# ProDocument_Affordable_2023-07-23.net
KiCad netlist of a schematic drawn in EasyEDA Pro
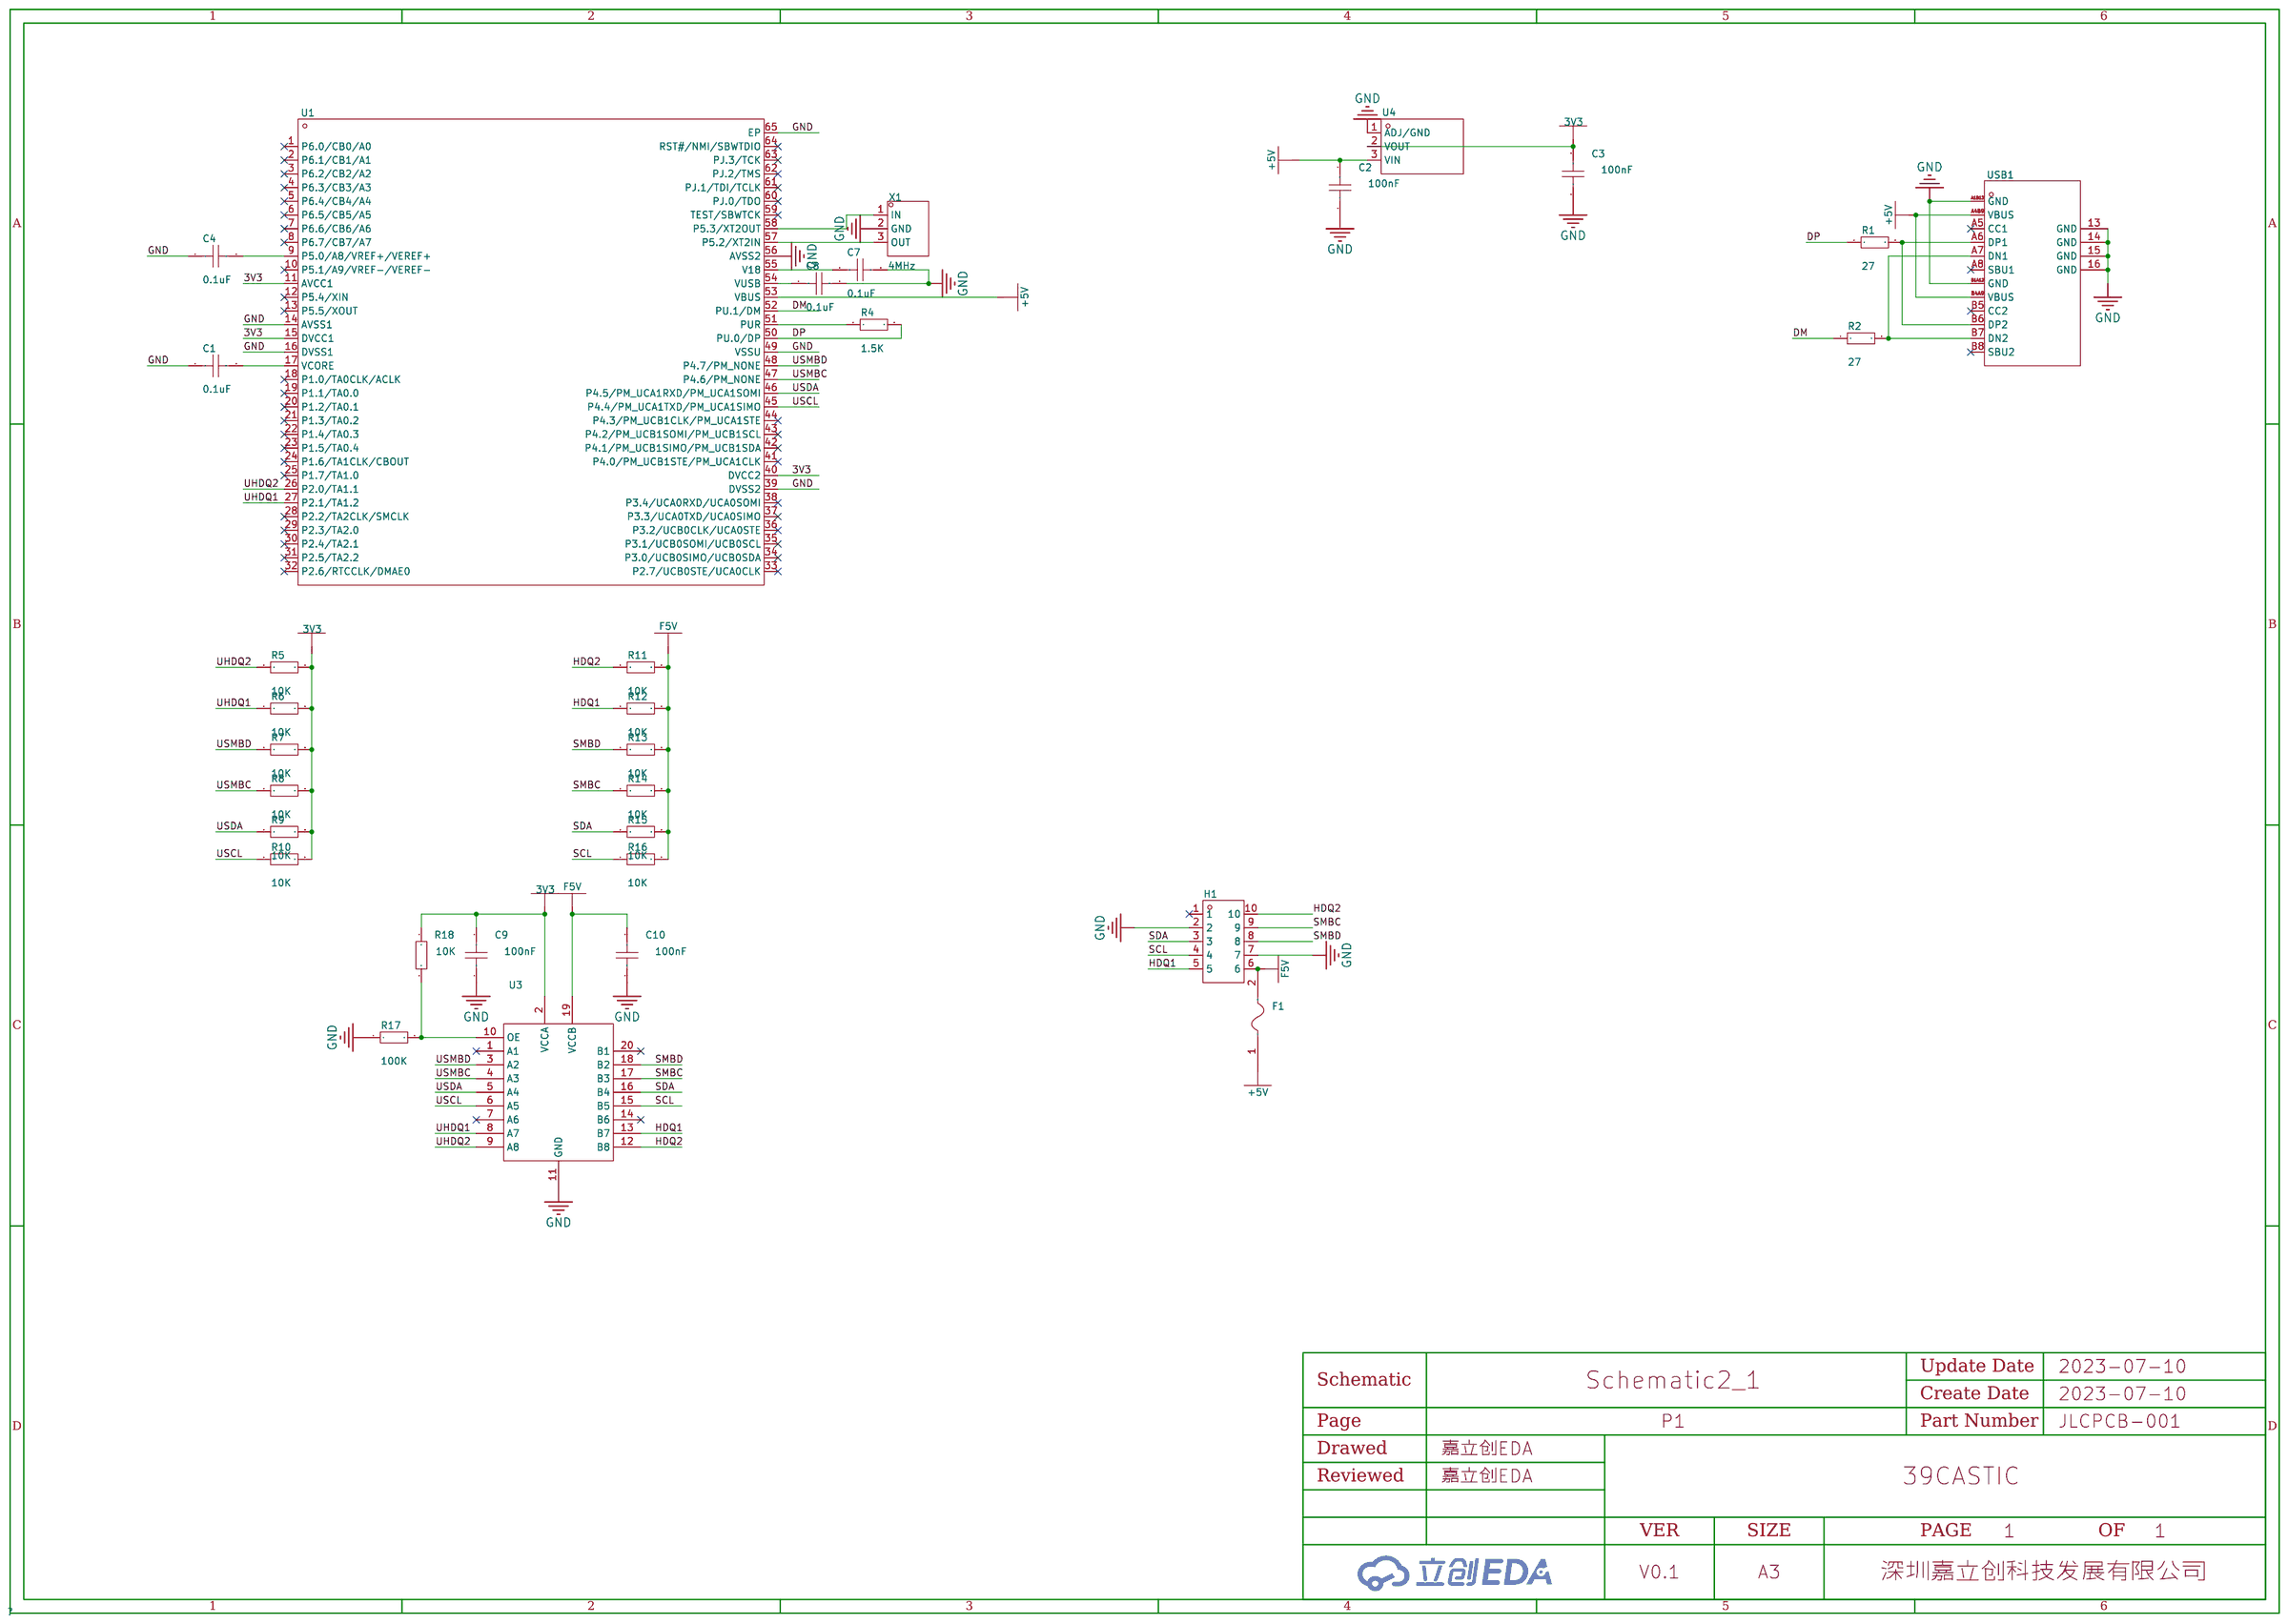
[diagram p0: schematic sheet]

(export (version "E")
  (design (tool "Eeschema 10.0.6"))
  (components
    (comp (ref "C1")
      (value "0.1uF")
      (footprint "easyedapro:C0603_1")
      (description "容值:100nF;精度:±10%;额定电压:50V;温度系数:X7R;")
      (libsource (lib "easyedapro") (part "C1210X7R475K630NT"))
    )
    (comp (ref "C2")
      (value "100nF")
      (footprint "easyedapro:C0603_1")
      (description "容值:100nF;精度:±10%;额定电压:50V;温度系数:X7R;")
      (libsource (lib "easyedapro") (part "C1210X7R475K630NT"))
    )
    (comp (ref "C3")
      (value "100nF")
      (footprint "easyedapro:C0603_1")
      (description "容值:100nF;精度:±10%;额定电压:50V;温度系数:X7R;")
      (libsource (lib "easyedapro") (part "C1210X7R475K630NT"))
    )
    (comp (ref "C4")
      (value "0.1uF")
      (footprint "easyedapro:C0603_1")
      (description "容值:100nF;精度:±10%;额定电压:50V;温度系数:X7R;")
      (libsource (lib "easyedapro") (part "C1210X7R475K630NT"))
    )
    (comp (ref "C7")
      (value "0.1uF")
      (footprint "easyedapro:C0603_1")
      (description "容值:100nF;精度:±10%;额定电压:50V;温度系数:X7R;")
      (libsource (lib "easyedapro") (part "C1210X7R475K630NT"))
    )
    (comp (ref "C8")
      (value "0.1uF")
      (footprint "easyedapro:C0603_1")
      (description "容值:100nF;精度:±10%;额定电压:50V;温度系数:X7R;")
      (libsource (lib "easyedapro") (part "C1210X7R475K630NT"))
    )
    (comp (ref "C9")
      (value "100nF")
      (footprint "easyedapro:C0603_1")
      (description "容值:100nF;精度:±10%;额定电压:50V;温度系数:X7R;")
      (libsource (lib "easyedapro") (part "C1210X7R475K630NT"))
    )
    (comp (ref "C10")
      (value "100nF")
      (footprint "easyedapro:C0603_1")
      (description "容值:100nF;精度:±10%;额定电压:50V;温度系数:X7R;")
      (libsource (lib "easyedapro") (part "C1210X7R475K630NT"))
    )
    (comp (ref "F1")
      (value "~")
      (footprint "easyedapro:F0805")
      (description "最大电压:6V;最大电流:40A;保持电流:500mA;跳闸电流:1A;")
      (fields (field (name "Manufacturer Part") "MF-PSMF050X-2") (field (name "Manufacturer") "BOURNS"))
      (libsource (lib "easyedapro") (part "MF-PSMF050X-2"))
    )
    (comp (ref "H1")
      (value "2*5p夹板_2.54mm")
      (footprint "easyedapro:2*5P_夹板_2.54MM")
      (libsource (lib "easyedapro") (part "2X5P 2.54 排母"))
    )
    (comp (ref "R1")
      (value "27")
      (footprint "easyedapro:R0603_1")
      (libsource (lib "easyedapro") (part "电阻_1"))
    )
    (comp (ref "R2")
      (value "27")
      (footprint "easyedapro:R0603_1")
      (libsource (lib "easyedapro") (part "电阻_1"))
    )
    (comp (ref "R4")
      (value "1.5K")
      (footprint "easyedapro:R0603_1")
      (libsource (lib "easyedapro") (part "电阻_1"))
    )
    (comp (ref "R5")
      (value "10K")
      (footprint "easyedapro:R0603_1")
      (libsource (lib "easyedapro") (part "电阻_1"))
    )
    (comp (ref "R6")
      (value "10K")
      (footprint "easyedapro:R0603_1")
      (libsource (lib "easyedapro") (part "电阻_1"))
    )
    (comp (ref "R7")
      (value "10K")
      (footprint "easyedapro:R0603_1")
      (libsource (lib "easyedapro") (part "电阻_1"))
    )
    (comp (ref "R8")
      (value "10K")
      (footprint "easyedapro:R0603_1")
      (libsource (lib "easyedapro") (part "电阻_1"))
    )
    (comp (ref "R9")
      (value "10K")
      (footprint "easyedapro:R0603_1")
      (libsource (lib "easyedapro") (part "电阻_1"))
    )
    (comp (ref "R10")
      (value "10K")
      (footprint "easyedapro:R0603_1")
      (libsource (lib "easyedapro") (part "电阻_1"))
    )
    (comp (ref "R11")
      (value "10K")
      (footprint "easyedapro:R0603_1")
      (libsource (lib "easyedapro") (part "电阻_1"))
    )
    (comp (ref "R12")
      (value "10K")
      (footprint "easyedapro:R0603_1")
      (libsource (lib "easyedapro") (part "电阻_1"))
    )
    (comp (ref "R13")
      (value "10K")
      (footprint "easyedapro:R0603_1")
      (libsource (lib "easyedapro") (part "电阻_1"))
    )
    (comp (ref "R14")
      (value "10K")
      (footprint "easyedapro:R0603_1")
      (libsource (lib "easyedapro") (part "电阻_1"))
    )
    (comp (ref "R15")
      (value "10K")
      (footprint "easyedapro:R0603_1")
      (libsource (lib "easyedapro") (part "电阻_1"))
    )
    (comp (ref "R16")
      (value "10K")
      (footprint "easyedapro:R0603_1")
      (libsource (lib "easyedapro") (part "电阻_1"))
    )
    (comp (ref "R17")
      (value "100K")
      (footprint "easyedapro:R0603_1")
      (libsource (lib "easyedapro") (part "电阻_1"))
    )
    (comp (ref "R18")
      (value "10K")
      (footprint "easyedapro:R0603_1")
      (libsource (lib "easyedapro") (part "电阻_1"))
    )
    (comp (ref "U1")
      (value "~")
      (footprint "easyedapro:QFN-64_L9.0-W9.0-P0.50-BL-EP4.3")
      (description "CPU位数:16-Bit;CPU内核:CPUXV2;主频（MAX):25MHz;工作电压:1.8V ~ 3.6V;")
      (fields (field (name "Manufacturer Part") "MSP430F5528IRGCR") (field (name "Manufacturer") "TI(德州仪器)"))
      (libsource (lib "easyedapro") (part "MSP430F5528IRGCR"))
    )
    (comp (ref "U3")
      (value "~")
      (footprint "easyedapro:TSSOP-20_L6.5-W4.4-P0.65-LS6.4-BL")
      (fields (field (name "Manufacturer Part") "TXS0108EPWR") (field (name "Manufacturer") "TI(德州仪器)"))
      (libsource (lib "easyedapro") (part "TXS0108EPWR"))
    )
    (comp (ref "U4")
      (value "~")
      (footprint "easyedapro:SOT-89-3_L4.5-W2.5-P1.50-LS4.2-BR")
      (description "输出类型:-;")
      (fields (field (name "Manufacturer Part") "AMS1117-5.0") (field (name "Manufacturer") "Slkor(萨科微)"))
      (libsource (lib "easyedapro") (part "AMS1117-5.0_C880753"))
    )
    (comp (ref "USB1")
      (value "~")
      (footprint "easyedapro:USB-C-SMD_TYPEC-304-BCP16")
      (description "连接器类型:Type-C;标准:USB 3.1;公母:母座;触点数量:16.0;端口数量:1;安装方式:卧贴;额定电流 - 电源:3A;工作温度范围:-25~+85;焊接温度(最大值):260;")
      (fields (field (name "Manufacturer Part") "TYPEC-304-BCP16") (field (name "Manufacturer") "XUNPU(讯普)"))
      (libsource (lib "easyedapro") (part "TYPEC-304-BCP16"))
    )
    (comp (ref "X1")
      (value "4MHz")
      (footprint "easyedapro:OSC-SMD_3P-L4.5-W2.0")
      (description "频率:4MHz;频率容差:±0.5%;内藏负载电容:39pF;谐振阻抗:60Ω;")
      (fields
        (field (name "Manufacturer Part") "CSTCR4M00G55B-R0")
        (field (name "Manufacturer") "muRata(村田)")
      )
      (libsource (lib "easyedapro") (part "CSTCR4M00G55B-R0"))
    )
  )
  (nets
    (net (code "1") (name "+5V") (class "Default")
      (node (ref "C2") (pin "2") (pinfunction "2_2") (pintype "input"))
      (node (ref "F1") (pin "1") (pinfunction "1_1") (pintype "input"))
      (node (ref "U1") (pin "53") (pinfunction "VBUS_53") (pintype "input"))
      (node (ref "U4") (pin "3") (pinfunction "VIN_3") (pintype "input"))
      (node (ref "USB1") (pin "A4B9") (pinfunction "VBUS_A4B9") (pintype "input"))
      (node (ref "USB1") (pin "B4A9") (pinfunction "VBUS_B4A9") (pintype "input"))
    )
    (net (code "2") (name "/DM") (class "Default")
      (node (ref "R2") (pin "1") (pinfunction "1_1") (pintype "input"))
      (node (ref "U1") (pin "52") (pinfunction "PU.1/DM_52") (pintype "input"))
    )
    (net (code "3") (name "/DP") (class "Default")
      (node (ref "R1") (pin "1") (pinfunction "1_1") (pintype "input"))
      (node (ref "R4") (pin "2") (pinfunction "2_2") (pintype "input"))
      (node (ref "U1") (pin "50") (pinfunction "PU.0/DP_50") (pintype "input"))
    )
    (net (code "4") (name "/HDQ1") (class "Default")
      (node (ref "H1") (pin "5") (pinfunction "5_5") (pintype "input"))
      (node (ref "R12") (pin "1") (pinfunction "1_1") (pintype "input"))
      (node (ref "U3") (pin "13") (pinfunction "B7_13") (pintype "input"))
    )
    (net (code "5") (name "/HDQ2") (class "Default")
      (node (ref "H1") (pin "10") (pinfunction "10_10") (pintype "input"))
      (node (ref "R11") (pin "1") (pinfunction "1_1") (pintype "input"))
      (node (ref "U3") (pin "12") (pinfunction "B8_12") (pintype "input"))
    )
    (net (code "6") (name "/SCL") (class "Default")
      (node (ref "H1") (pin "4") (pinfunction "4_4") (pintype "input"))
      (node (ref "R16") (pin "1") (pinfunction "1_1") (pintype "input"))
      (node (ref "U3") (pin "15") (pinfunction "B5_15") (pintype "input"))
    )
    (net (code "7") (name "/SDA") (class "Default")
      (node (ref "H1") (pin "3") (pinfunction "3_3") (pintype "input"))
      (node (ref "R15") (pin "1") (pinfunction "1_1") (pintype "input"))
      (node (ref "U3") (pin "16") (pinfunction "B4_16") (pintype "input"))
    )
    (net (code "8") (name "/SMBC") (class "Default")
      (node (ref "H1") (pin "9") (pinfunction "9_9") (pintype "input"))
      (node (ref "R14") (pin "1") (pinfunction "1_1") (pintype "input"))
      (node (ref "U3") (pin "17") (pinfunction "B3_17") (pintype "input"))
    )
    (net (code "9") (name "/SMBD") (class "Default")
      (node (ref "H1") (pin "8") (pinfunction "8_8") (pintype "input"))
      (node (ref "R13") (pin "1") (pinfunction "1_1") (pintype "input"))
      (node (ref "U3") (pin "18") (pinfunction "B2_18") (pintype "input"))
    )
    (net (code "10") (name "/UHDQ1") (class "Default")
      (node (ref "R6") (pin "1") (pinfunction "1_1") (pintype "input"))
      (node (ref "U1") (pin "27") (pinfunction "P2.1/TA1.2_27") (pintype "input"))
      (node (ref "U3") (pin "8") (pinfunction "A7_8") (pintype "input"))
    )
    (net (code "11") (name "/UHDQ2") (class "Default")
      (node (ref "R5") (pin "1") (pinfunction "1_1") (pintype "input"))
      (node (ref "U1") (pin "26") (pinfunction "P2.0/TA1.1_26") (pintype "input"))
      (node (ref "U3") (pin "9") (pinfunction "A8_9") (pintype "input"))
    )
    (net (code "12") (name "/USCL") (class "Default")
      (node (ref "R10") (pin "1") (pinfunction "1_1") (pintype "input"))
      (node (ref "U1") (pin "45") (pinfunction "P4.4/PM_UCA1TXD/PM_UCA1SIMO_45") (pintype "input"))
      (node (ref "U3") (pin "6") (pinfunction "A5_6") (pintype "input"))
    )
    (net (code "13") (name "/USDA") (class "Default")
      (node (ref "R9") (pin "1") (pinfunction "1_1") (pintype "input"))
      (node (ref "U1") (pin "46") (pinfunction "P4.5/PM_UCA1RXD/PM_UCA1SOMI_46") (pintype "input"))
      (node (ref "U3") (pin "5") (pinfunction "A4_5") (pintype "input"))
    )
    (net (code "14") (name "/USMBC") (class "Default")
      (node (ref "R8") (pin "1") (pinfunction "1_1") (pintype "input"))
      (node (ref "U1") (pin "47") (pinfunction "P4.6/PM_NONE_47") (pintype "input"))
      (node (ref "U3") (pin "4") (pinfunction "A3_4") (pintype "input"))
    )
    (net (code "15") (name "/USMBD") (class "Default")
      (node (ref "R7") (pin "1") (pinfunction "1_1") (pintype "input"))
      (node (ref "U1") (pin "48") (pinfunction "P4.7/PM_NONE_48") (pintype "input"))
      (node (ref "U3") (pin "3") (pinfunction "A2_3") (pintype "input"))
    )
    (net (code "16") (name "3V3") (class "Default")
      (node (ref "C3") (pin "2") (pinfunction "2_2") (pintype "input"))
      (node (ref "C9") (pin "2") (pinfunction "2_2") (pintype "input"))
      (node (ref "R10") (pin "2") (pinfunction "2_2") (pintype "input"))
      (node (ref "R18") (pin "2") (pinfunction "2_2") (pintype "input"))
      (node (ref "R5") (pin "2") (pinfunction "2_2") (pintype "input"))
      (node (ref "R6") (pin "2") (pinfunction "2_2") (pintype "input"))
      (node (ref "R7") (pin "2") (pinfunction "2_2") (pintype "input"))
      (node (ref "R8") (pin "2") (pinfunction "2_2") (pintype "input"))
      (node (ref "R9") (pin "2") (pinfunction "2_2") (pintype "input"))
      (node (ref "U1") (pin "11") (pinfunction "AVCC1_11") (pintype "input"))
      (node (ref "U1") (pin "15") (pinfunction "DVCC1_15") (pintype "input"))
      (node (ref "U1") (pin "40") (pinfunction "DVCC2_40") (pintype "input"))
      (node (ref "U3") (pin "2") (pinfunction "VCCA_2") (pintype "input"))
      (node (ref "U4") (pin "2") (pinfunction "VOUT_2") (pintype "input"))
    )
    (net (code "17") (name "F5V") (class "Default")
      (node (ref "C10") (pin "2") (pinfunction "2_2") (pintype "input"))
      (node (ref "F1") (pin "2") (pinfunction "2_2") (pintype "input"))
      (node (ref "H1") (pin "6") (pinfunction "6_6") (pintype "input"))
      (node (ref "R11") (pin "2") (pinfunction "2_2") (pintype "input"))
      (node (ref "R12") (pin "2") (pinfunction "2_2") (pintype "input"))
      (node (ref "R13") (pin "2") (pinfunction "2_2") (pintype "input"))
      (node (ref "R14") (pin "2") (pinfunction "2_2") (pintype "input"))
      (node (ref "R15") (pin "2") (pinfunction "2_2") (pintype "input"))
      (node (ref "R16") (pin "2") (pinfunction "2_2") (pintype "input"))
      (node (ref "U3") (pin "19") (pinfunction "VCCB_19") (pintype "input"))
    )
    (net (code "18") (name "GND") (class "Default")
      (node (ref "C1") (pin "1") (pinfunction "1_1") (pintype "input"))
      (node (ref "C10") (pin "1") (pinfunction "1_1") (pintype "input"))
      (node (ref "C2") (pin "1") (pinfunction "1_1") (pintype "input"))
      (node (ref "C3") (pin "1") (pinfunction "1_1") (pintype "input"))
      (node (ref "C4") (pin "1") (pinfunction "1_1") (pintype "input"))
      (node (ref "C7") (pin "2") (pinfunction "2_2") (pintype "input"))
      (node (ref "C8") (pin "2") (pinfunction "2_2") (pintype "input"))
      (node (ref "C9") (pin "1") (pinfunction "1_1") (pintype "input"))
      (node (ref "H1") (pin "2") (pinfunction "2_2") (pintype "input"))
      (node (ref "H1") (pin "7") (pinfunction "7_7") (pintype "input"))
      (node (ref "R17") (pin "1") (pinfunction "1_1") (pintype "input"))
      (node (ref "U1") (pin "14") (pinfunction "AVSS1_14") (pintype "input"))
      (node (ref "U1") (pin "16") (pinfunction "DVSS1_16") (pintype "input"))
      (node (ref "U1") (pin "39") (pinfunction "DVSS2_39") (pintype "input"))
      (node (ref "U1") (pin "49") (pinfunction "VSSU_49") (pintype "input"))
      (node (ref "U1") (pin "56") (pinfunction "AVSS2_56") (pintype "input"))
      (node (ref "U1") (pin "65") (pinfunction "EP_65") (pintype "input"))
      (node (ref "U3") (pin "11") (pinfunction "GND_11") (pintype "input"))
      (node (ref "U4") (pin "1") (pinfunction "ADJ/GND_1") (pintype "input"))
      (node (ref "USB1") (pin "13") (pinfunction "GND_13") (pintype "input"))
      (node (ref "USB1") (pin "14") (pinfunction "GND_14") (pintype "input"))
      (node (ref "USB1") (pin "15") (pinfunction "GND_15") (pintype "input"))
      (node (ref "USB1") (pin "16") (pinfunction "GND_16") (pintype "input"))
      (node (ref "USB1") (pin "A1B12") (pinfunction "GND_A1B12") (pintype "input"))
      (node (ref "USB1") (pin "B1A12") (pinfunction "GND_B1A12") (pintype "input"))
      (node (ref "X1") (pin "2") (pinfunction "GND_2") (pintype "input"))
    )
    (net (code "19") (name "Net-(U1-P5.0{slash}A8{slash}VREF+{slash}VEREF+)") (class "Default")
      (node (ref "C4") (pin "2") (pinfunction "2_2") (pintype "input"))
      (node (ref "U1") (pin "9") (pinfunction "P5.0/A8/VREF+/VEREF+_9") (pintype "input"))
    )
    (net (code "20") (name "Net-(U1-P5.2{slash}XT2IN)") (class "Default")
      (node (ref "U1") (pin "57") (pinfunction "P5.2/XT2IN_57") (pintype "input"))
      (node (ref "X1") (pin "3") (pinfunction "OUT_3") (pintype "input"))
    )
    (net (code "21") (name "Net-(U1-P5.3{slash}XT2OUT)") (class "Default")
      (node (ref "U1") (pin "58") (pinfunction "P5.3/XT2OUT_58") (pintype "input"))
      (node (ref "X1") (pin "1") (pinfunction "IN_1") (pintype "input"))
    )
    (net (code "22") (name "Net-(U1-PUR)") (class "Default")
      (node (ref "R4") (pin "1") (pinfunction "1_1") (pintype "input"))
      (node (ref "U1") (pin "51") (pinfunction "PUR_51") (pintype "input"))
    )
    (net (code "23") (name "Net-(U1-V18)") (class "Default")
      (node (ref "C7") (pin "1") (pinfunction "1_1") (pintype "input"))
      (node (ref "U1") (pin "55") (pinfunction "V18_55") (pintype "input"))
    )
    (net (code "24") (name "Net-(U1-VCORE)") (class "Default")
      (node (ref "C1") (pin "2") (pinfunction "2_2") (pintype "input"))
      (node (ref "U1") (pin "17") (pinfunction "VCORE_17") (pintype "input"))
    )
    (net (code "25") (name "Net-(U1-VUSB)") (class "Default")
      (node (ref "C8") (pin "1") (pinfunction "1_1") (pintype "input"))
      (node (ref "U1") (pin "54") (pinfunction "VUSB_54") (pintype "input"))
    )
    (net (code "26") (name "Net-(U3-OE)") (class "Default")
      (node (ref "R17") (pin "2") (pinfunction "2_2") (pintype "input"))
      (node (ref "R18") (pin "1") (pinfunction "1_1") (pintype "input"))
      (node (ref "U3") (pin "10") (pinfunction "OE_10") (pintype "input"))
    )
    (net (code "27") (name "Net-(USB1-DN1)") (class "Default")
      (node (ref "R2") (pin "2") (pinfunction "2_2") (pintype "input"))
      (node (ref "USB1") (pin "A7") (pinfunction "DN1_A7") (pintype "input"))
      (node (ref "USB1") (pin "B7") (pinfunction "DN2_B7") (pintype "input"))
    )
    (net (code "28") (name "Net-(USB1-DP1)") (class "Default")
      (node (ref "R1") (pin "2") (pinfunction "2_2") (pintype "input"))
      (node (ref "USB1") (pin "A6") (pinfunction "DP1_A6") (pintype "input"))
      (node (ref "USB1") (pin "B6") (pinfunction "DP2_B6") (pintype "input"))
    )
    (net (code "29") (name "unconnected-(H1-Pad1)") (class "Default")
      (node (ref "H1") (pin "1") (pinfunction "1_1") (pintype "input+no_connect"))
    )
    (net (code "30") (name "unconnected-(U1-P1.0{slash}TA0CLK{slash}ACLK-Pad18)") (class "Default")
      (node (ref "U1") (pin "18") (pinfunction "P1.0/TA0CLK/ACLK_18") (pintype "input+no_connect"))
    )
    (net (code "31") (name "unconnected-(U1-P1.1{slash}TA0.0-Pad19)") (class "Default")
      (node (ref "U1") (pin "19") (pinfunction "P1.1/TA0.0_19") (pintype "input+no_connect"))
    )
    (net (code "32") (name "unconnected-(U1-P1.2{slash}TA0.1-Pad20)") (class "Default")
      (node (ref "U1") (pin "20") (pinfunction "P1.2/TA0.1_20") (pintype "input+no_connect"))
    )
    (net (code "33") (name "unconnected-(U1-P1.3{slash}TA0.2-Pad21)") (class "Default")
      (node (ref "U1") (pin "21") (pinfunction "P1.3/TA0.2_21") (pintype "input+no_connect"))
    )
    (net (code "34") (name "unconnected-(U1-P1.4{slash}TA0.3-Pad22)") (class "Default")
      (node (ref "U1") (pin "22") (pinfunction "P1.4/TA0.3_22") (pintype "input+no_connect"))
    )
    (net (code "35") (name "unconnected-(U1-P1.5{slash}TA0.4-Pad23)") (class "Default")
      (node (ref "U1") (pin "23") (pinfunction "P1.5/TA0.4_23") (pintype "input+no_connect"))
    )
    (net (code "36") (name "unconnected-(U1-P1.6{slash}TA1CLK{slash}CBOUT-Pad24)") (class "Default")
      (node (ref "U1") (pin "24") (pinfunction "P1.6/TA1CLK/CBOUT_24") (pintype "input+no_connect"))
    )
    (net (code "37") (name "unconnected-(U1-P1.7{slash}TA1.0-Pad25)") (class "Default")
      (node (ref "U1") (pin "25") (pinfunction "P1.7/TA1.0_25") (pintype "input+no_connect"))
    )
    (net (code "38") (name "unconnected-(U1-P2.2{slash}TA2CLK{slash}SMCLK-Pad28)") (class "Default")
      (node (ref "U1") (pin "28") (pinfunction "P2.2/TA2CLK/SMCLK_28") (pintype "input+no_connect"))
    )
    (net (code "39") (name "unconnected-(U1-P2.3{slash}TA2.0-Pad29)") (class "Default")
      (node (ref "U1") (pin "29") (pinfunction "P2.3/TA2.0_29") (pintype "input+no_connect"))
    )
    (net (code "40") (name "unconnected-(U1-P2.4{slash}TA2.1-Pad30)") (class "Default")
      (node (ref "U1") (pin "30") (pinfunction "P2.4/TA2.1_30") (pintype "input+no_connect"))
    )
    (net (code "41") (name "unconnected-(U1-P2.5{slash}TA2.2-Pad31)") (class "Default")
      (node (ref "U1") (pin "31") (pinfunction "P2.5/TA2.2_31") (pintype "input+no_connect"))
    )
    (net (code "42") (name "unconnected-(U1-P2.6{slash}RTCCLK{slash}DMAE0-Pad32)") (class "Default")
      (node (ref "U1") (pin "32") (pinfunction "P2.6/RTCCLK/DMAE0_32") (pintype "input+no_connect"))
    )
    (net (code "43") (name "unconnected-(U1-P2.7{slash}UCB0STE{slash}UCA0CLK-Pad33)") (class "Default")
      (node (ref "U1") (pin "33") (pinfunction "P2.7/UCB0STE/UCA0CLK_33") (pintype "input+no_connect"))
    )
    (net (code "44") (name "unconnected-(U1-P3.0{slash}UCB0SIMO{slash}UCB0SDA-Pad34)") (class "Default")
      (node (ref "U1") (pin "34") (pinfunction "P3.0/UCB0SIMO/UCB0SDA_34") (pintype "input+no_connect"))
    )
    (net (code "45") (name "unconnected-(U1-P3.1{slash}UCB0SOMI{slash}UCB0SCL-Pad35)") (class "Default")
      (node (ref "U1") (pin "35") (pinfunction "P3.1/UCB0SOMI/UCB0SCL_35") (pintype "input+no_connect"))
    )
    (net (code "46") (name "unconnected-(U1-P3.2{slash}UCB0CLK{slash}UCA0STE-Pad36)") (class "Default")
      (node (ref "U1") (pin "36") (pinfunction "P3.2/UCB0CLK/UCA0STE_36") (pintype "input+no_connect"))
    )
    (net (code "47") (name "unconnected-(U1-P3.3{slash}UCA0TXD{slash}UCA0SIMO-Pad37)") (class "Default")
      (node (ref "U1") (pin "37") (pinfunction "P3.3/UCA0TXD/UCA0SIMO_37") (pintype "input+no_connect"))
    )
    (net (code "48") (name "unconnected-(U1-P3.4{slash}UCA0RXD{slash}UCA0SOMI-Pad38)") (class "Default")
      (node (ref "U1") (pin "38") (pinfunction "P3.4/UCA0RXD/UCA0SOMI_38") (pintype "input+no_connect"))
    )
    (net (code "49") (name "unconnected-(U1-P4.0{slash}PM_UCB1STE{slash}PM_UCA1CLK-Pad41)") (class "Default")
      (node (ref "U1") (pin "41") (pinfunction "P4.0/PM_UCB1STE/PM_UCA1CLK_41") (pintype "input+no_connect"))
    )
    (net (code "50") (name "unconnected-(U1-P4.1{slash}PM_UCB1SIMO{slash}PM_UCB1SDA-Pad42)") (class "Default")
      (node (ref "U1") (pin "42") (pinfunction "P4.1/PM_UCB1SIMO/PM_UCB1SDA_42") (pintype "input+no_connect"))
    )
    (net (code "51") (name "unconnected-(U1-P4.2{slash}PM_UCB1SOMI{slash}PM_UCB1SCL-Pad43)") (class "Default")
      (node (ref "U1") (pin "43") (pinfunction "P4.2/PM_UCB1SOMI/PM_UCB1SCL_43") (pintype "input+no_connect"))
    )
    (net (code "52") (name "unconnected-(U1-P4.3{slash}PM_UCB1CLK{slash}PM_UCA1STE-Pad44)") (class "Default")
      (node (ref "U1") (pin "44") (pinfunction "P4.3/PM_UCB1CLK/PM_UCA1STE_44") (pintype "input+no_connect"))
    )
    (net (code "53") (name "unconnected-(U1-P5.1{slash}A9{slash}VREF-{slash}VEREF--Pad10)") (class "Default")
      (node (ref "U1") (pin "10") (pinfunction "P5.1/A9/VREF-/VEREF-_10") (pintype "input+no_connect"))
    )
    (net (code "54") (name "unconnected-(U1-P5.4{slash}XIN-Pad12)") (class "Default")
      (node (ref "U1") (pin "12") (pinfunction "P5.4/XIN_12") (pintype "input+no_connect"))
    )
    (net (code "55") (name "unconnected-(U1-P5.5{slash}XOUT-Pad13)") (class "Default")
      (node (ref "U1") (pin "13") (pinfunction "P5.5/XOUT_13") (pintype "input+no_connect"))
    )
    (net (code "56") (name "unconnected-(U1-P6.0{slash}CB0{slash}A0-Pad1)") (class "Default")
      (node (ref "U1") (pin "1") (pinfunction "P6.0/CB0/A0_1") (pintype "input+no_connect"))
    )
    (net (code "57") (name "unconnected-(U1-P6.1{slash}CB1{slash}A1-Pad2)") (class "Default")
      (node (ref "U1") (pin "2") (pinfunction "P6.1/CB1/A1_2") (pintype "input+no_connect"))
    )
    (net (code "58") (name "unconnected-(U1-P6.2{slash}CB2{slash}A2-Pad3)") (class "Default")
      (node (ref "U1") (pin "3") (pinfunction "P6.2/CB2/A2_3") (pintype "input+no_connect"))
    )
    (net (code "59") (name "unconnected-(U1-P6.3{slash}CB3{slash}A3-Pad4)") (class "Default")
      (node (ref "U1") (pin "4") (pinfunction "P6.3/CB3/A3_4") (pintype "input+no_connect"))
    )
    (net (code "60") (name "unconnected-(U1-P6.4{slash}CB4{slash}A4-Pad5)") (class "Default")
      (node (ref "U1") (pin "5") (pinfunction "P6.4/CB4/A4_5") (pintype "input+no_connect"))
    )
    (net (code "61") (name "unconnected-(U1-P6.5{slash}CB5{slash}A5-Pad6)") (class "Default")
      (node (ref "U1") (pin "6") (pinfunction "P6.5/CB5/A5_6") (pintype "input+no_connect"))
    )
    (net (code "62") (name "unconnected-(U1-P6.6{slash}CB6{slash}A6-Pad7)") (class "Default")
      (node (ref "U1") (pin "7") (pinfunction "P6.6/CB6/A6_7") (pintype "input+no_connect"))
    )
    (net (code "63") (name "unconnected-(U1-P6.7{slash}CB7{slash}A7-Pad8)") (class "Default")
      (node (ref "U1") (pin "8") (pinfunction "P6.7/CB7/A7_8") (pintype "input+no_connect"))
    )
    (net (code "64") (name "unconnected-(U1-PJ.0{slash}TDO-Pad60)") (class "Default")
      (node (ref "U1") (pin "60") (pinfunction "PJ.0/TDO_60") (pintype "input+no_connect"))
    )
    (net (code "65") (name "unconnected-(U1-PJ.1{slash}TDI{slash}TCLK-Pad61)") (class "Default")
      (node (ref "U1") (pin "61") (pinfunction "PJ.1/TDI/TCLK_61") (pintype "input+no_connect"))
    )
    (net (code "66") (name "unconnected-(U1-PJ.2{slash}TMS-Pad62)") (class "Default")
      (node (ref "U1") (pin "62") (pinfunction "PJ.2/TMS_62") (pintype "input+no_connect"))
    )
    (net (code "67") (name "unconnected-(U1-PJ.3{slash}TCK-Pad63)") (class "Default")
      (node (ref "U1") (pin "63") (pinfunction "PJ.3/TCK_63") (pintype "input+no_connect"))
    )
    (net (code "68") (name "unconnected-(U1-RST#{slash}NMI{slash}SBWTDIO-Pad64)") (class "Default")
      (node (ref "U1") (pin "64") (pinfunction "RST#/NMI/SBWTDIO_64") (pintype "input+no_connect"))
    )
    (net (code "69") (name "unconnected-(U1-TEST{slash}SBWTCK-Pad59)") (class "Default")
      (node (ref "U1") (pin "59") (pinfunction "TEST/SBWTCK_59") (pintype "input+no_connect"))
    )
    (net (code "70") (name "unconnected-(U3-A1-Pad1)") (class "Default")
      (node (ref "U3") (pin "1") (pinfunction "A1_1") (pintype "input+no_connect"))
    )
    (net (code "71") (name "unconnected-(U3-A6-Pad7)") (class "Default")
      (node (ref "U3") (pin "7") (pinfunction "A6_7") (pintype "input+no_connect"))
    )
    (net (code "72") (name "unconnected-(U3-B1-Pad20)") (class "Default")
      (node (ref "U3") (pin "20") (pinfunction "B1_20") (pintype "input+no_connect"))
    )
    (net (code "73") (name "unconnected-(U3-B6-Pad14)") (class "Default")
      (node (ref "U3") (pin "14") (pinfunction "B6_14") (pintype "input+no_connect"))
    )
    (net (code "74") (name "unconnected-(USB1-CC1-PadA5)") (class "Default")
      (node (ref "USB1") (pin "A5") (pinfunction "CC1_A5") (pintype "input+no_connect"))
    )
    (net (code "75") (name "unconnected-(USB1-CC2-PadB5)") (class "Default")
      (node (ref "USB1") (pin "B5") (pinfunction "CC2_B5") (pintype "input+no_connect"))
    )
    (net (code "76") (name "unconnected-(USB1-SBU1-PadA8)") (class "Default")
      (node (ref "USB1") (pin "A8") (pinfunction "SBU1_A8") (pintype "input+no_connect"))
    )
    (net (code "77") (name "unconnected-(USB1-SBU2-PadB8)") (class "Default")
      (node (ref "USB1") (pin "B8") (pinfunction "SBU2_B8") (pintype "input+no_connect"))
    )
  )
)
